# paddle.net
KiCad netlist of a schematic drawn in EAGLE
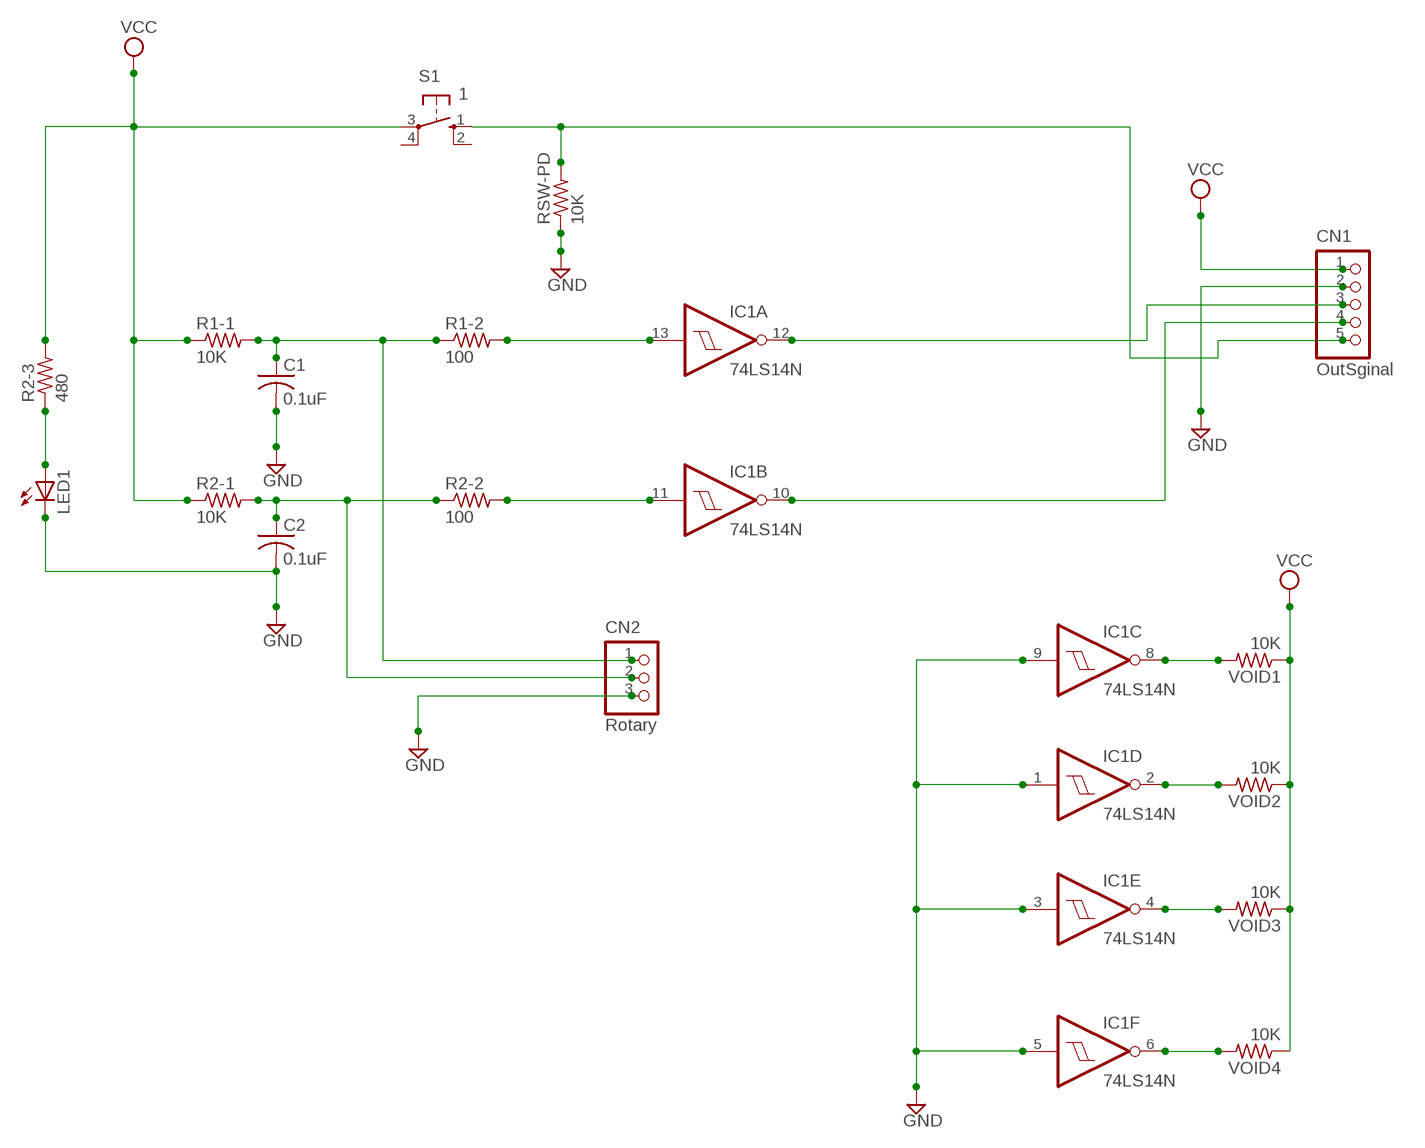
[diagram p0: schematic, sheet 1]

(export (version "E")
  (design (tool "Eeschema 10.0.6"))
  (components
    (comp (ref "C1")
      (value "0.1uF")
      (footprint "eagle-import:C050-050X075")
      (libsource (lib "eagle-import") (part "C-US050-050X075"))
    )
    (comp (ref "C2")
      (value "0.1uF")
      (footprint "eagle-import:C050-050X075")
      (libsource (lib "eagle-import") (part "C-US050-050X075"))
    )
    (comp (ref "CN1")
      (value "OutSginal")
      (footprint "eagle-import:B5B-PH-K-S")
      (libsource (lib "eagle-import") (part "B5B-PH-K-S"))
    )
    (comp (ref "CN2")
      (value "Rotary")
      (footprint "eagle-import:B3B-PH-K-S")
      (libsource (lib "eagle-import") (part "B3B-PH-K-S"))
    )
    (comp (ref "IC1")
      (value "74LS14N")
      (footprint "eagle-import:DIL14")
      (libsource (lib "eagle-import") (part "7414NLS"))
    )
    (comp (ref "LED1")
      (value "LED3MM")
      (footprint "eagle-import:LED3MM")
      (libsource (lib "eagle-import") (part "LED3MM"))
    )
    (comp (ref "R1-1")
      (value "10K")
      (footprint "eagle-import:0207_2V")
      (libsource (lib "eagle-import") (part "R-US_0207/2V"))
    )
    (comp (ref "R1-2")
      (value "100")
      (footprint "eagle-import:0207_2V")
      (libsource (lib "eagle-import") (part "R-US_0207/2V"))
    )
    (comp (ref "R2-1")
      (value "10K")
      (footprint "eagle-import:0207_2V")
      (libsource (lib "eagle-import") (part "R-US_0207/2V"))
    )
    (comp (ref "R2-2")
      (value "100")
      (footprint "eagle-import:0207_2V")
      (libsource (lib "eagle-import") (part "R-US_0207/2V"))
    )
    (comp (ref "R2-3")
      (value "480")
      (footprint "eagle-import:0207_2V")
      (libsource (lib "eagle-import") (part "R-US_0207/2V"))
    )
    (comp (ref "RSW-PD")
      (value "10K")
      (footprint "eagle-import:0207_2V")
      (libsource (lib "eagle-import") (part "R-US_0207/2V"))
    )
    (comp (ref "S1")
      (value "1")
      (footprint "eagle-import:B3F-10XX")
      (fields (field (name "MPN") "B3F-1000"))
      (libsource (lib "eagle-import") (part "10-XX"))
    )
    (comp (ref "VOID1")
      (value "10K")
      (footprint "eagle-import:0207_2V")
      (libsource (lib "eagle-import") (part "R-US_0207/2V"))
    )
    (comp (ref "VOID2")
      (value "10K")
      (footprint "eagle-import:0207_2V")
      (libsource (lib "eagle-import") (part "R-US_0207/2V"))
    )
    (comp (ref "VOID3")
      (value "10K")
      (footprint "eagle-import:0207_2V")
      (libsource (lib "eagle-import") (part "R-US_0207/2V"))
    )
    (comp (ref "VOID4")
      (value "10K")
      (footprint "eagle-import:0207_2V")
      (libsource (lib "eagle-import") (part "R-US_0207/2V"))
    )
  )
  (nets
    (net (code "1") (name "GND") (class "Default")
      (node (ref "C1") (pin "2") (pinfunction "2_2") (pintype "passive"))
      (node (ref "C2") (pin "2") (pinfunction "2_2") (pintype "passive"))
      (node (ref "CN1") (pin "2") (pinfunction "2_2") (pintype "passive"))
      (node (ref "CN2") (pin "3") (pinfunction "3_3") (pintype "passive"))
      (node (ref "IC1") (pin "1") (pinfunction "I_1") (pintype "input"))
      (node (ref "IC1") (pin "3") (pinfunction "I_3") (pintype "input"))
      (node (ref "IC1") (pin "5") (pinfunction "I_5") (pintype "input"))
      (node (ref "IC1") (pin "9") (pinfunction "I_9") (pintype "input"))
      (node (ref "LED1") (pin "K") (pinfunction "C_K") (pintype "passive"))
      (node (ref "RSW-PD") (pin "1") (pinfunction "1_1") (pintype "passive"))
    )
    (net (code "2") (name "Net-(C1-Pad1)") (class "Default")
      (node (ref "C1") (pin "1") (pinfunction "1_1") (pintype "passive"))
      (node (ref "CN2") (pin "1") (pinfunction "1_1") (pintype "passive"))
      (node (ref "R1-1") (pin "2") (pinfunction "2_2") (pintype "passive"))
      (node (ref "R1-2") (pin "1") (pinfunction "1_1") (pintype "passive"))
    )
    (net (code "3") (name "Net-(C2-Pad1)") (class "Default")
      (node (ref "C2") (pin "1") (pinfunction "1_1") (pintype "passive"))
      (node (ref "CN2") (pin "2") (pinfunction "2_2") (pintype "passive"))
      (node (ref "R2-1") (pin "2") (pinfunction "2_2") (pintype "passive"))
      (node (ref "R2-2") (pin "1") (pinfunction "1_1") (pintype "passive"))
    )
    (net (code "4") (name "Net-(IC1A-I)") (class "Default")
      (node (ref "IC1") (pin "13") (pinfunction "I_13") (pintype "input"))
      (node (ref "R1-2") (pin "2") (pinfunction "2_2") (pintype "passive"))
    )
    (net (code "5") (name "Net-(IC1A-O)") (class "Default")
      (node (ref "CN1") (pin "3") (pinfunction "3_3") (pintype "passive"))
      (node (ref "IC1") (pin "12") (pinfunction "O_12") (pintype "output"))
    )
    (net (code "6") (name "Net-(IC1B-I)") (class "Default")
      (node (ref "IC1") (pin "11") (pinfunction "I_11") (pintype "input"))
      (node (ref "R2-2") (pin "2") (pinfunction "2_2") (pintype "passive"))
    )
    (net (code "7") (name "Net-(IC1B-O)") (class "Default")
      (node (ref "CN1") (pin "4") (pinfunction "4_4") (pintype "passive"))
      (node (ref "IC1") (pin "10") (pinfunction "O_10") (pintype "output"))
    )
    (net (code "8") (name "Net-(IC1C-O)") (class "Default")
      (node (ref "IC1") (pin "8") (pinfunction "O_8") (pintype "output"))
      (node (ref "VOID1") (pin "2") (pinfunction "2_2") (pintype "passive"))
    )
    (net (code "9") (name "Net-(IC1D-O)") (class "Default")
      (node (ref "IC1") (pin "2") (pinfunction "O_2") (pintype "output"))
      (node (ref "VOID2") (pin "2") (pinfunction "2_2") (pintype "passive"))
    )
    (net (code "10") (name "Net-(IC1E-O)") (class "Default")
      (node (ref "IC1") (pin "4") (pinfunction "O_4") (pintype "output"))
      (node (ref "VOID3") (pin "2") (pinfunction "2_2") (pintype "passive"))
    )
    (net (code "11") (name "Net-(IC1F-O)") (class "Default")
      (node (ref "IC1") (pin "6") (pinfunction "O_6") (pintype "output"))
      (node (ref "VOID4") (pin "2") (pinfunction "2_2") (pintype "passive"))
    )
    (net (code "12") (name "Net-(LED1-PadA)") (class "Default")
      (node (ref "LED1") (pin "A") (pinfunction "A_A") (pintype "passive"))
      (node (ref "R2-3") (pin "1") (pinfunction "1_1") (pintype "passive"))
    )
    (net (code "13") (name "Net-(S1-S)") (class "Default")
      (node (ref "CN1") (pin "5") (pinfunction "5_5") (pintype "passive"))
      (node (ref "RSW-PD") (pin "2") (pinfunction "2_2") (pintype "passive"))
      (node (ref "S1") (pin "1") (pinfunction "S_1") (pintype "passive"))
    )
    (net (code "14") (name "VCC") (class "Default")
      (node (ref "CN1") (pin "1") (pinfunction "1_1") (pintype "passive"))
      (node (ref "R1-1") (pin "1") (pinfunction "1_1") (pintype "passive"))
      (node (ref "R2-1") (pin "1") (pinfunction "1_1") (pintype "passive"))
      (node (ref "R2-3") (pin "2") (pinfunction "2_2") (pintype "passive"))
      (node (ref "S1") (pin "3") (pinfunction "P_3") (pintype "passive"))
      (node (ref "VOID1") (pin "1") (pinfunction "1_1") (pintype "passive"))
      (node (ref "VOID2") (pin "1") (pinfunction "1_1") (pintype "passive"))
      (node (ref "VOID3") (pin "1") (pinfunction "1_1") (pintype "passive"))
      (node (ref "VOID4") (pin "1") (pinfunction "1_1") (pintype "passive"))
    )
    (net (code "15") (name "unconnected-(S1-P1-Pad4)") (class "Default")
      (node (ref "S1") (pin "4") (pinfunction "P1_4") (pintype "passive"))
    )
    (net (code "16") (name "unconnected-(S1-S1-Pad2)") (class "Default")
      (node (ref "S1") (pin "2") (pinfunction "S1_2") (pintype "passive"))
    )
  )
)
